# ESP_Grow_Main_V2_3_Con.net
KiCad netlist of a schematic drawn in Altium Designer
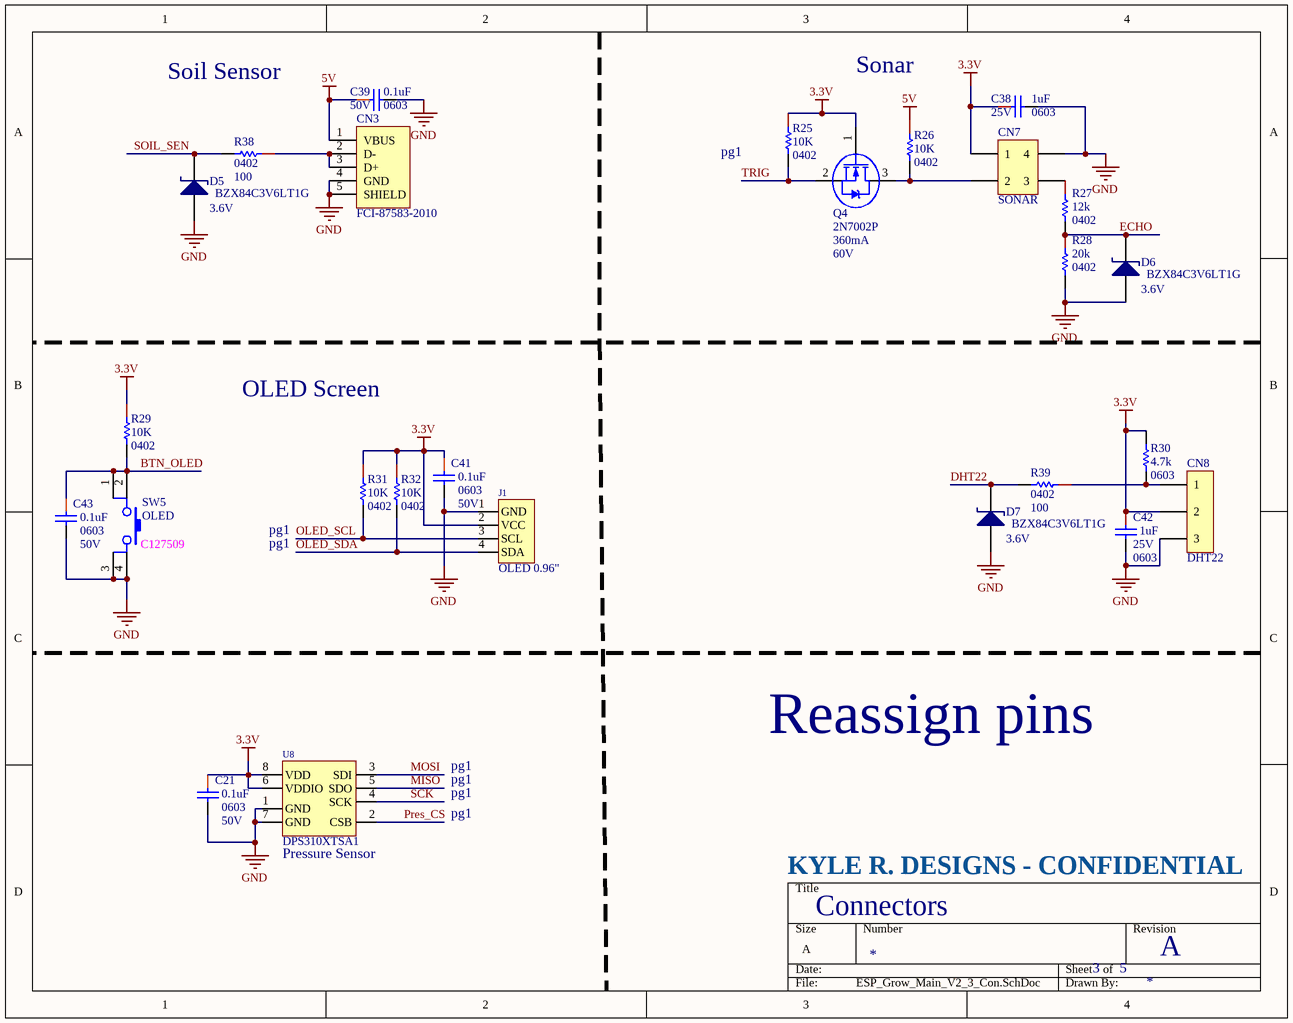
[diagram p0: ESP_Grow_Main_V2_3_Con.SchDoc]

(export (version "E")
  (design (tool "Eeschema 10.0.6"))
  (components
    (comp (ref "C21")
      (value "0.1uF")
      (footprint "CAPC0603(1608)_L")
      (description "100NF 50V 0603")
      (fields
        (field (name "MANUFACTURER") "YAGEO")
        (field (name "MANUFACTURER PART NUMBER") "CC0603KRX7R9BB104")
        (field (name "CAPACITANCE") "0.1uF")
        (field (name "PACKAGE / CASE") "0603")
        (field (name "VOLTAGE - RATED") "50V")
      )
      (libsource (lib "JLCPCB_Capacitors") (part "0.1uF_0603"))
    )
    (comp (ref "C38")
      (value "1uF")
      (footprint "CAPC0603(1608)_N")
      (description "1uF 0603 25V")
      (fields
        (field (name "MANUFACTURER") "TDK Corporation")
        (field (name "MANUFACTURER PART NUMBER") "CGA3E1X7R1E105K080AC")
        (field (name "VOLTAGE - RATED") "25V")
        (field (name "PACKAGE / CASE") "0603")
      )
      (libsource (lib "OLogic-Passive") (part "CAP CER 1UF 25V 10% X7R 0603"))
    )
    (comp (ref "C39")
      (value "0.1uF")
      (footprint "CAPC0603(1608)_L")
      (description "100NF 50V 0603")
      (fields
        (field (name "MANUFACTURER") "YAGEO")
        (field (name "MANUFACTURER PART NUMBER") "CC0603KRX7R9BB104")
        (field (name "CAPACITANCE") "0.1uF")
        (field (name "PACKAGE / CASE") "0603")
        (field (name "VOLTAGE - RATED") "50V")
      )
      (libsource (lib "JLCPCB_Capacitors") (part "0.1uF_0603"))
    )
    (comp (ref "C41")
      (value "0.1uF")
      (footprint "CAPC0603(1608)_L")
      (description "100NF 50V 0603")
      (fields
        (field (name "MANUFACTURER") "YAGEO")
        (field (name "MANUFACTURER PART NUMBER") "CC0603KRX7R9BB104")
        (field (name "CAPACITANCE") "0.1uF")
        (field (name "PACKAGE / CASE") "0603")
        (field (name "VOLTAGE - RATED") "50V")
      )
      (libsource (lib "JLCPCB_Capacitors") (part "0.1uF_0603"))
    )
    (comp (ref "C42")
      (value "1uF")
      (footprint "CAPC0603(1608)_N")
      (description "1uF 0603 25V")
      (fields
        (field (name "MANUFACTURER") "TDK Corporation")
        (field (name "MANUFACTURER PART NUMBER") "CGA3E1X7R1E105K080AC")
        (field (name "VOLTAGE - RATED") "25V")
        (field (name "PACKAGE / CASE") "0603")
      )
      (libsource (lib "OLogic-Passive") (part "CAP CER 1UF 25V 10% X7R 0603"))
    )
    (comp (ref "C43")
      (value "0.1uF")
      (footprint "CAPC0603(1608)_L")
      (description "100NF 50V 0603")
      (fields
        (field (name "MANUFACTURER") "YAGEO")
        (field (name "MANUFACTURER PART NUMBER") "CC0603KRX7R9BB104")
        (field (name "CAPACITANCE") "0.1uF")
        (field (name "PACKAGE / CASE") "0603")
        (field (name "VOLTAGE - RATED") "50V")
      )
      (libsource (lib "JLCPCB_Capacitors") (part "0.1uF_0603"))
    )
    (comp (ref "CN3")
      (value "FCI-87583-2010")
      (footprint "87583-2010")
      (description "USB-A Receptacle")
      (fields (field (name "MANUFACTURER PART NUMBER") "87583-2010BLF") (field (name "MANUFACTURER") "FCI"))
      (libsource (lib "OLogic Nexus Vault") (part "FCI-87583-2010"))
    )
    (comp (ref "CN7")
      (value "SONAR")
      (footprint "Molex 2x2 Microfit 90deg")
      (description "Molex Microfit 2x2 90deg Header")
      (fields
        (field (name "MANUFACTURER") "Molex Inc")
        (field (name "MANUFACTURER PART NUMBER") "0430450400")
      )
      (libsource (lib "OLogic-Connectors") (part "MICROFIT 3.0 HDR 90deg 4CKT"))
    )
    (comp (ref "CN8")
      (value "DHT22")
      (footprint "Molex 1x3 Microfit 90deg")
      (description "Molex Microfit 1x3 90deg Header")
      (fields
        (field (name "MANUFACTURER") "Molex Inc")
        (field (name "MANUFACTURER PART NUMBER") "0436500304")
      )
      (libsource (lib "OLogic-Connectors") (part "MICROFIT 3.0 HDR 90deg 3CKT"))
    )
    (comp (ref "D5")
      (value "BZX84C3V6LT1G")
      (footprint "SOT23")
      (description "DIODE ZENER 3.6V 225MW SOT23-3")
      (fields (field (name "TOLERANCE") "6%") (field (name "VOLTAGE RATING (DC)") "3.6V"))
      (libsource (lib "OLogic Nexus Vault") (part "BZX84C3V6LT1G"))
    )
    (comp (ref "D6")
      (value "BZX84C3V6LT1G")
      (footprint "SOT23")
      (description "DIODE ZENER 3.6V 225MW SOT23-3")
      (fields (field (name "TOLERANCE") "6%") (field (name "VOLTAGE RATING (DC)") "3.6V"))
      (libsource (lib "OLogic Nexus Vault") (part "BZX84C3V6LT1G"))
    )
    (comp (ref "D7")
      (value "BZX84C3V6LT1G")
      (footprint "SOT23")
      (description "DIODE ZENER 3.6V 225MW SOT23-3")
      (fields (field (name "TOLERANCE") "6%") (field (name "VOLTAGE RATING (DC)") "3.6V"))
      (libsource (lib "OLogic Nexus Vault") (part "BZX84C3V6LT1G"))
    )
    (comp (ref "J1")
      (value "OLED 0.96\"")
      (footprint "OLED_0.96_I2C")
      (description "SSD1306 I2C OLED 0.96\"")
      (libsource (lib "Kyle_Lib_04-20-19") (part "OLED_0.96_I2C"))
    )
    (comp (ref "Q4")
      (value "2N7002P")
      (footprint "SOT23")
      (description "MOSFET N-CH 60V 0.36A SOT-23")
      (fields
        (field (name "CONTINUOUS DRAIN CURRENT (ID)") "360mA")
        (field (name "DRAIN TO SOURCE VOLTAGE (VDSS)") "60V")
      )
      (libsource (lib "OLogic Nexus Vault") (part "2N7002P,235"))
    )
    (comp (ref "R25")
      (value "0402WGF1002TCE")
      (footprint "RESC0402(1005)_N")
      (description "10KOHMS ±1% 1/10W 0402")
      (fields (field (name "RESISTANCE") "10K") (field (name "PACKAGE") "0402"))
      (libsource (lib "JLCPCB_Resistors") (part "10k_0402"))
    )
    (comp (ref "R26")
      (value "0402WGF1002TCE")
      (footprint "RESC0402(1005)_N")
      (description "10KOHMS ±1% 1/10W 0402")
      (fields (field (name "RESISTANCE") "10K") (field (name "PACKAGE") "0402"))
      (libsource (lib "JLCPCB_Resistors") (part "10k_0402"))
    )
    (comp (ref "R27")
      (value "RES 12K OHM 1% 1/16W 0402")
      (footprint "RESC0402(1005)_M")
      (description "12 kOhms ±1% 0.063W, 1/16W Chip Resistor 0402 (1005 Metric) Automotive AEC-Q200 Thick Film")
      (fields
        (field (name "PACKAGE (IMPERIAL)") "0402")
        (field (name "RESISTANCE") "12k")
        (field (name "POWER") "63mW")
        (field (name "TOLERANCE") "1%")
      )
      (libsource (lib "OLogic Nexus Vault") (part "=Resistance"))
    )
    (comp (ref "R28")
      (value "20K")
      (footprint "RESC0402(1005)_L")
      (description "RES 20K OHM 1% 1/10W 0402")
      (fields
        (field (name "PACKAGE (IMPERIAL)") "0402")
        (field (name "POWER") "63mW")
        (field (name "TOLERANCE") "1%")
        (field (name "RESISTANCE") "20k")
      )
      (libsource (lib "OLogic Nexus Vault") (part "=Resistance"))
    )
    (comp (ref "R29")
      (value "0402WGF1002TCE")
      (footprint "RESC0402(1005)_N")
      (description "10KOHMS ±1% 1/10W 0402")
      (fields (field (name "RESISTANCE") "10K") (field (name "PACKAGE") "0402"))
      (libsource (lib "JLCPCB_Resistors") (part "10k_0402"))
    )
    (comp (ref "R30")
      (value "4.7K")
      (footprint "RESC0603(1608)_N")
      (description "4.7K 0603")
      (fields
        (field (name "MANUFACTURER") "Panasonic Electronic Components")
        (field (name "MANUFACTURER PART NUMBER") "ERJ-3GEYJ472V")
        (field (name "RESISTANCE (OHMS)") "4.7k")
        (field (name "PACKAGE / CASE") "0603")
      )
      (libsource (lib "OLogic-Passive") (part "RES 4.7K OHM 1/10W 5% 0603 SMD"))
    )
    (comp (ref "R31")
      (value "0402WGF1002TCE")
      (footprint "RESC0402(1005)_N")
      (description "10KOHMS ±1% 1/10W 0402")
      (fields (field (name "RESISTANCE") "10K") (field (name "PACKAGE") "0402"))
      (libsource (lib "JLCPCB_Resistors") (part "10k_0402"))
    )
    (comp (ref "R32")
      (value "0402WGF1002TCE")
      (footprint "RESC0402(1005)_N")
      (description "10KOHMS ±1% 1/10W 0402")
      (fields (field (name "RESISTANCE") "10K") (field (name "PACKAGE") "0402"))
      (libsource (lib "JLCPCB_Resistors") (part "10k_0402"))
    )
    (comp (ref "R38")
      (value "100")
      (footprint "RESC0402(1005)_M")
      (description "RES 100 OHM 1% 1/16W 0402")
      (fields
        (field (name "PACKAGE (IMPERIAL)") "0402")
        (field (name "POWER") "63mW")
        (field (name "RESISTANCE") "100")
        (field (name "TOLERANCE") "1%")
      )
      (libsource (lib "") (part "=Resistance_1"))
    )
    (comp (ref "R39")
      (value "100")
      (footprint "RESC0402(1005)_M")
      (description "RES 100 OHM 1% 1/16W 0402")
      (fields
        (field (name "PACKAGE (IMPERIAL)") "0402")
        (field (name "POWER") "63mW")
        (field (name "RESISTANCE") "100")
        (field (name "TOLERANCE") "1%")
      )
      (libsource (lib "") (part "=Resistance_1"))
    )
    (comp (ref "SW5")
      (value "OLED")
      (footprint "SW TACT Red 6mm x 6mm")
      (description "SWITCH TACTILE SPST-NO 0.05A 12V")
      (fields
        (field (name "MANUFACTURER") "C&K")
        (field (name "MANUFACTURER PART NUMBER") "PTS645SM43SMTR92 LFS")
      )
      (libsource (lib "OLogic-Switches") (part "PTS645SM43SMTR92 LFS"))
    )
    (comp (ref "U8")
      (value "DPS310XTSA1")
      (footprint "Infineon_PG-VLGA-8")
      (description "SENSOR PRESSURE CAPACITIVE")
      (libsource (lib "Kyle-Sensors") (part "DPS310"))
    )
  )
  (nets
    (net (code "1") (name "/BTN_OLED") (class "Default")
      (node (ref "C43") (pin "1") (pinfunction "1_1") (pintype "passive"))
      (node (ref "R29") (pin "2") (pinfunction "2_2") (pintype "passive"))
      (node (ref "SW5") (pin "1") (pinfunction "1_1") (pintype "passive"))
      (node (ref "SW5") (pin "2") (pinfunction "2_2") (pintype "passive"))
    )
    (net (code "2") (name "/DHT22") (class "Default")
      (node (ref "D7") (pin "3") (pinfunction "K_3") (pintype "passive"))
      (node (ref "R39") (pin "2") (pinfunction "2_2") (pintype "passive"))
    )
    (net (code "3") (name "/ECHO") (class "Default")
      (node (ref "D6") (pin "3") (pinfunction "K_3") (pintype "passive"))
      (node (ref "R27") (pin "2") (pinfunction "2_2") (pintype "passive"))
      (node (ref "R28") (pin "1") (pinfunction "1_1") (pintype "passive"))
    )
    (net (code "4") (name "/MISO") (class "Default")
      (node (ref "U8") (pin "5") (pinfunction "SDO_5") (pintype "passive"))
    )
    (net (code "5") (name "/MOSI") (class "Default")
      (node (ref "U8") (pin "3") (pinfunction "SDI_3") (pintype "passive"))
    )
    (net (code "6") (name "/OLED_SCL") (class "Default")
      (node (ref "J1") (pin "3") (pinfunction "SCL_3") (pintype "passive"))
      (node (ref "R31") (pin "2") (pinfunction "2_2") (pintype "passive"))
    )
    (net (code "7") (name "/OLED_SDA") (class "Default")
      (node (ref "J1") (pin "4") (pinfunction "SDA_4") (pintype "passive"))
      (node (ref "R32") (pin "2") (pinfunction "2_2") (pintype "passive"))
    )
    (net (code "8") (name "/Pres_CS") (class "Default")
      (node (ref "U8") (pin "2") (pinfunction "CSB_2") (pintype "passive"))
    )
    (net (code "9") (name "/SCK") (class "Default")
      (node (ref "U8") (pin "4") (pinfunction "SCK_4") (pintype "passive"))
    )
    (net (code "10") (name "/SOIL_SEN") (class "Default")
      (node (ref "D5") (pin "3") (pinfunction "K_3") (pintype "passive"))
      (node (ref "R38") (pin "2") (pinfunction "2_2") (pintype "passive"))
    )
    (net (code "11") (name "/TRIG") (class "Default")
      (node (ref "Q4") (pin "2") (pinfunction "S_2") (pintype "passive"))
      (node (ref "R25") (pin "2") (pinfunction "2_2") (pintype "passive"))
    )
    (net (code "12") (name "3.3V") (class "Default")
      (node (ref "C21") (pin "1") (pinfunction "1_1") (pintype "passive"))
      (node (ref "C38") (pin "1") (pinfunction "1_1") (pintype "passive"))
      (node (ref "C41") (pin "1") (pinfunction "1_1") (pintype "passive"))
      (node (ref "C42") (pin "1") (pinfunction "1_1") (pintype "passive"))
      (node (ref "CN7") (pin "1") (pinfunction "1_1") (pintype "passive"))
      (node (ref "CN8") (pin "2") (pinfunction "2_2") (pintype "passive"))
      (node (ref "J1") (pin "2") (pinfunction "VCC_2") (pintype "passive"))
      (node (ref "Q4") (pin "1") (pinfunction "G_1") (pintype "passive"))
      (node (ref "R25") (pin "1") (pinfunction "1_1") (pintype "passive"))
      (node (ref "R29") (pin "1") (pinfunction "1_1") (pintype "passive"))
      (node (ref "R30") (pin "2") (pinfunction "2_2") (pintype "passive"))
      (node (ref "R31") (pin "1") (pinfunction "1_1") (pintype "passive"))
      (node (ref "R32") (pin "1") (pinfunction "1_1") (pintype "passive"))
      (node (ref "U8") (pin "6") (pinfunction "VDDIO_6") (pintype "passive"))
      (node (ref "U8") (pin "8") (pinfunction "VDD_8") (pintype "passive"))
    )
    (net (code "13") (name "5V") (class "Default")
      (node (ref "C39") (pin "1") (pinfunction "1_1") (pintype "passive"))
      (node (ref "CN3") (pin "1") (pinfunction "VBUS_1") (pintype "power_in"))
      (node (ref "R26") (pin "1") (pinfunction "1_1") (pintype "passive"))
    )
    (net (code "14") (name "GND") (class "Default")
      (node (ref "C21") (pin "2") (pinfunction "2_2") (pintype "passive"))
      (node (ref "C38") (pin "2") (pinfunction "2_2") (pintype "passive"))
      (node (ref "C39") (pin "2") (pinfunction "2_2") (pintype "passive"))
      (node (ref "C41") (pin "2") (pinfunction "2_2") (pintype "passive"))
      (node (ref "C42") (pin "2") (pinfunction "2_2") (pintype "passive"))
      (node (ref "C43") (pin "2") (pinfunction "2_2") (pintype "passive"))
      (node (ref "CN3") (pin "4") (pinfunction "GND_4") (pintype "power_in"))
      (node (ref "CN3") (pin "5") (pinfunction "SHIELD_5") (pintype "power_in"))
      (node (ref "CN7") (pin "4") (pinfunction "4_4") (pintype "passive"))
      (node (ref "CN8") (pin "3") (pinfunction "3_3") (pintype "passive"))
      (node (ref "D5") (pin "1") (pinfunction "A_1") (pintype "passive"))
      (node (ref "D6") (pin "1") (pinfunction "A_1") (pintype "passive"))
      (node (ref "D7") (pin "1") (pinfunction "A_1") (pintype "passive"))
      (node (ref "J1") (pin "1") (pinfunction "GND_1") (pintype "passive"))
      (node (ref "R28") (pin "2") (pinfunction "2_2") (pintype "passive"))
      (node (ref "SW5") (pin "3") (pinfunction "3_3") (pintype "passive"))
      (node (ref "SW5") (pin "4") (pinfunction "4_4") (pintype "passive"))
      (node (ref "U8") (pin "1") (pinfunction "GND_1") (pintype "passive"))
      (node (ref "U8") (pin "7") (pinfunction "GND_7") (pintype "passive"))
    )
    (net (code "15") (name "Net-(CN3-D+)") (class "Default")
      (node (ref "CN3") (pin "2") (pinfunction "D-_2") (pintype "passive"))
      (node (ref "CN3") (pin "3") (pinfunction "D+_3") (pintype "passive"))
      (node (ref "R38") (pin "1") (pinfunction "1_1") (pintype "passive"))
    )
    (net (code "16") (name "Net-(CN7-Pad3)") (class "Default")
      (node (ref "CN7") (pin "3") (pinfunction "3_3") (pintype "passive"))
      (node (ref "R27") (pin "1") (pinfunction "1_1") (pintype "passive"))
    )
    (net (code "17") (name "Net-(CN8-Pad1)") (class "Default")
      (node (ref "CN8") (pin "1") (pinfunction "1_1") (pintype "passive"))
      (node (ref "R30") (pin "1") (pinfunction "1_1") (pintype "passive"))
      (node (ref "R39") (pin "1") (pinfunction "1_1") (pintype "passive"))
    )
    (net (code "18") (name "Net-(Q4-D)") (class "Default")
      (node (ref "CN7") (pin "2") (pinfunction "2_2") (pintype "passive"))
      (node (ref "Q4") (pin "3") (pinfunction "D_3") (pintype "passive"))
      (node (ref "R26") (pin "2") (pinfunction "2_2") (pintype "passive"))
    )
  )
)
